# SocikPI.net
KiCad netlist of a schematic drawn in EAGLE
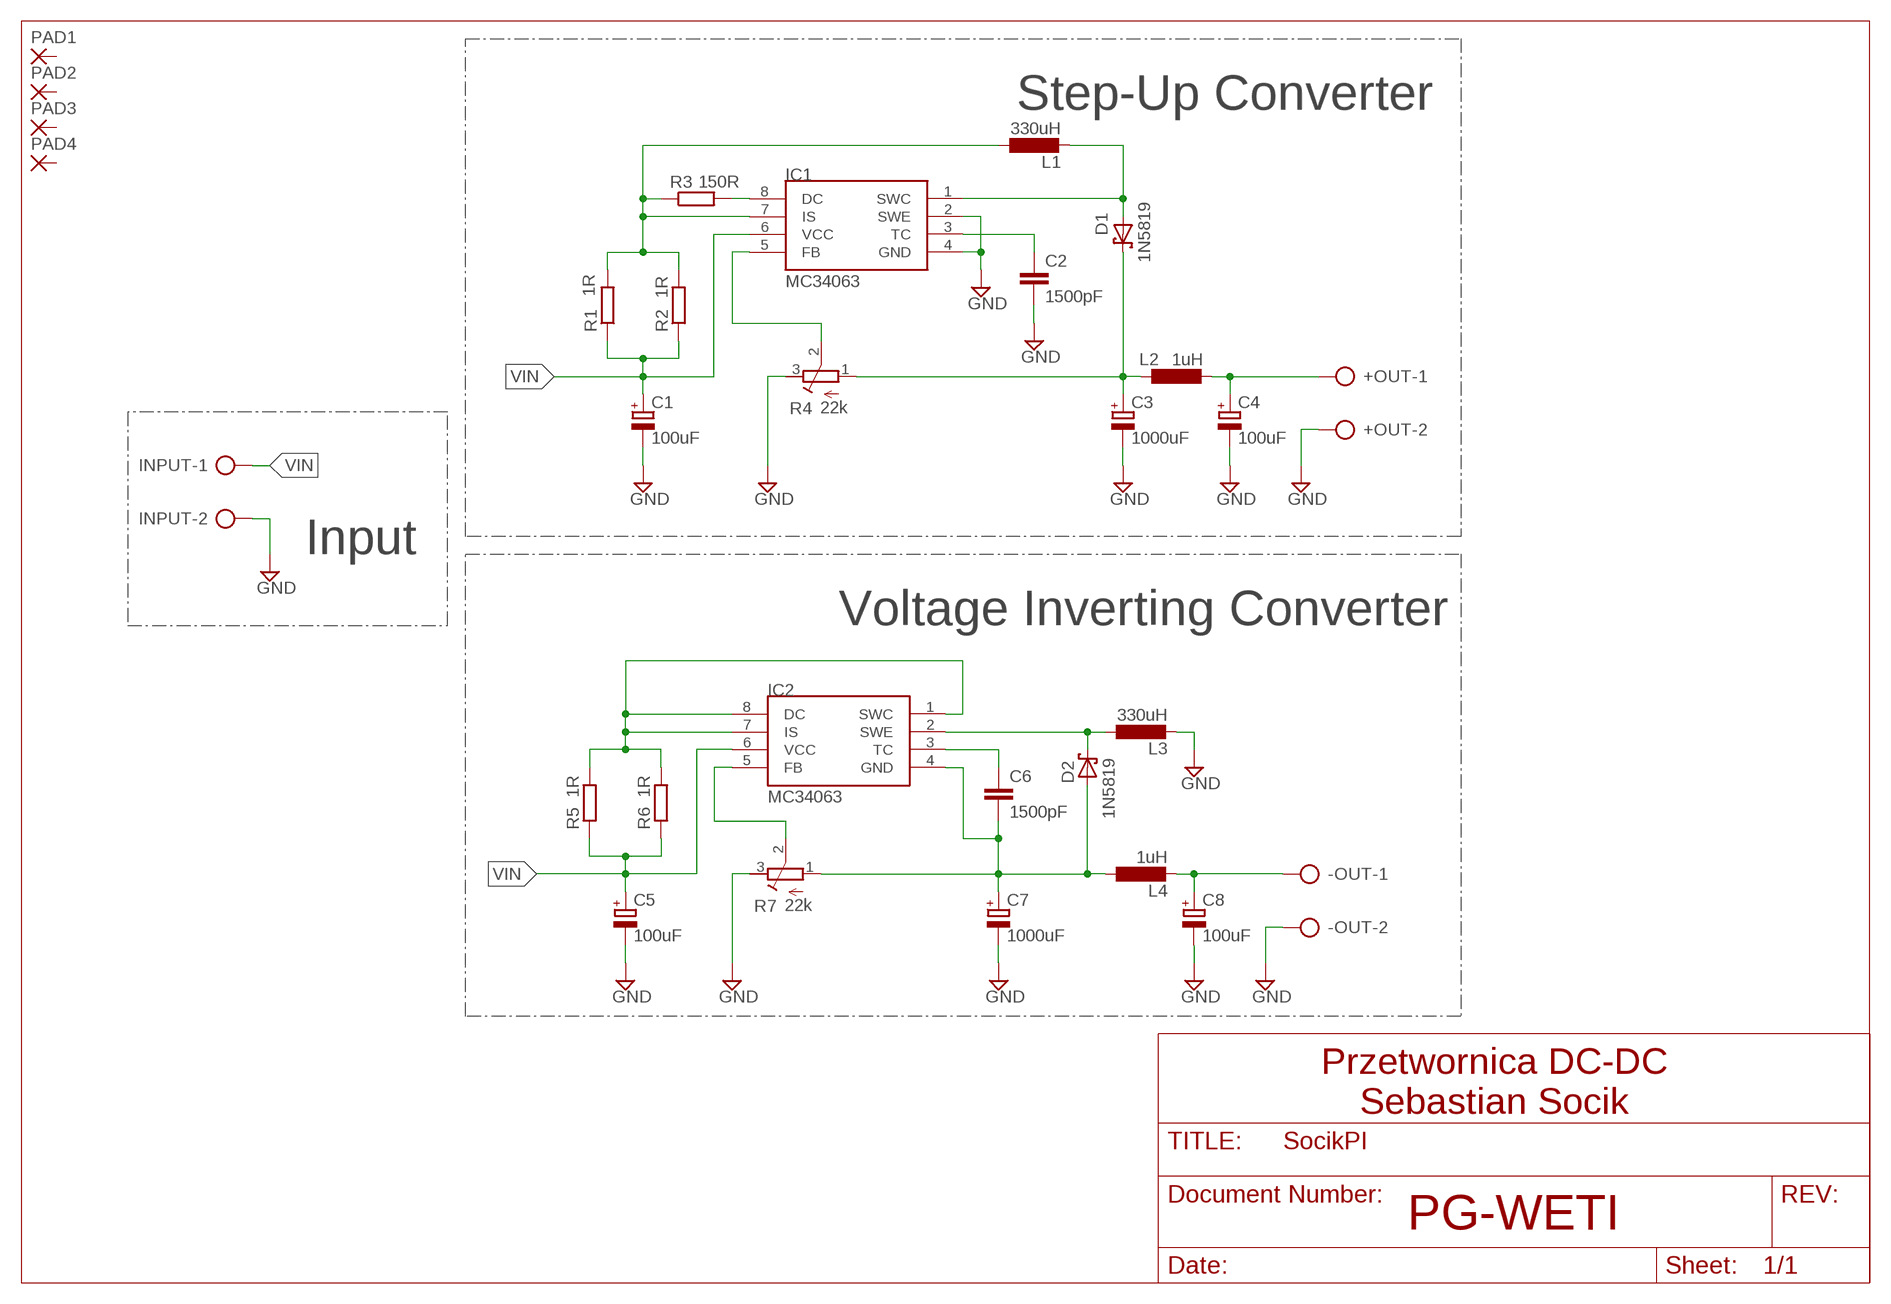
[diagram p0: schematic, sheet 1]

(export (version "E")
  (design (tool "Eeschema 10.0.6"))
  (components
    (comp (ref "+OUT")
      (value "CON-PTR500_AK500/2")
      (footprint "eagle-import:CON-PTR500_AK500_2")
      (libsource (lib "eagle-import") (part "CON-PTR500_AK500/2"))
    )
    (comp (ref "-OUT")
      (value "CON-PTR500_AK500/2")
      (footprint "eagle-import:CON-PTR500_AK500_2")
      (libsource (lib "eagle-import") (part "CON-PTR500_AK500/2"))
    )
    (comp (ref "C1")
      (value "100uF")
      (footprint "eagle-import:RCL_E2,5-7")
      (libsource (lib "eagle-import") (part "RCL_CPOL-EUE2.5-7"))
    )
    (comp (ref "C2")
      (value "1500pF")
      (footprint "eagle-import:C1206")
      (libsource (lib "eagle-import") (part "C-EUC1206"))
    )
    (comp (ref "C3")
      (value "1000uF")
      (footprint "eagle-import:RCL_E5-10,5")
      (libsource (lib "eagle-import") (part "RCL_CPOL-EUE5-10.5"))
    )
    (comp (ref "C4")
      (value "100uF")
      (footprint "eagle-import:RCL_E2,5-7")
      (libsource (lib "eagle-import") (part "RCL_CPOL-EUE2.5-7"))
    )
    (comp (ref "C5")
      (value "100uF")
      (footprint "eagle-import:RCL_E2,5-7")
      (libsource (lib "eagle-import") (part "RCL_CPOL-EUE2.5-7"))
    )
    (comp (ref "C6")
      (value "1500pF")
      (footprint "eagle-import:C1206")
      (libsource (lib "eagle-import") (part "C-EUC1206"))
    )
    (comp (ref "C7")
      (value "1000uF")
      (footprint "eagle-import:RCL_E5-10,5")
      (libsource (lib "eagle-import") (part "RCL_CPOL-EUE5-10.5"))
    )
    (comp (ref "C8")
      (value "100uF")
      (footprint "eagle-import:RCL_E2,5-7")
      (libsource (lib "eagle-import") (part "RCL_CPOL-EUE2.5-7"))
    )
    (comp (ref "D1")
      (value "1N5819")
      (footprint "eagle-import:DIODE_DO41-7.6")
      (libsource (lib "eagle-import") (part "DIODE_1N5819-B"))
    )
    (comp (ref "D2")
      (value "1N5819")
      (footprint "eagle-import:DIODE_DO41-7.6")
      (libsource (lib "eagle-import") (part "DIODE_1N5819-B"))
    )
    (comp (ref "IC1")
      (value "MC34063")
      (footprint "eagle-import:MC34063_DIL08")
      (libsource (lib "eagle-import") (part "MC34063_MC34063AP"))
    )
    (comp (ref "IC2")
      (value "MC34063")
      (footprint "eagle-import:MC34063_DIL08")
      (libsource (lib "eagle-import") (part "MC34063_MC34063AP"))
    )
    (comp (ref "INPUT")
      (value "CON-PTR500_AK500/2")
      (footprint "eagle-import:CON-PTR500_AK500_2")
      (libsource (lib "eagle-import") (part "CON-PTR500_AK500/2"))
    )
    (comp (ref "L1")
      (value "330uH")
      (footprint "eagle-import:RCL_0207_10")
      (libsource (lib "eagle-import") (part "RCL_L-EU0207/10"))
    )
    (comp (ref "L2")
      (value "1uH")
      (footprint "eagle-import:RCL_0207_10")
      (libsource (lib "eagle-import") (part "RCL_L-EU0207/10"))
    )
    (comp (ref "L3")
      (value "330uH")
      (footprint "eagle-import:RCL_0207_10")
      (libsource (lib "eagle-import") (part "RCL_L-EU0207/10"))
    )
    (comp (ref "L4")
      (value "1uH")
      (footprint "eagle-import:RCL_0207_10")
      (libsource (lib "eagle-import") (part "RCL_L-EU0207/10"))
    )
    (comp (ref "PAD1")
      (value "2,54/1,1")
      (footprint "eagle-import:2,54_1,1")
      (libsource (lib "eagle-import") (part "2,54/1,1"))
    )
    (comp (ref "PAD2")
      (value "2,54/1,1")
      (footprint "eagle-import:2,54_1,1")
      (libsource (lib "eagle-import") (part "2,54/1,1"))
    )
    (comp (ref "PAD3")
      (value "2,54/1,1")
      (footprint "eagle-import:2,54_1,1")
      (libsource (lib "eagle-import") (part "2,54/1,1"))
    )
    (comp (ref "PAD4")
      (value "2,54/1,1")
      (footprint "eagle-import:2,54_1,1")
      (libsource (lib "eagle-import") (part "2,54/1,1"))
    )
    (comp (ref "R1")
      (value "1R")
      (footprint "eagle-import:R1206")
      (libsource (lib "eagle-import") (part "R-EU_R1206"))
    )
    (comp (ref "R2")
      (value "1R")
      (footprint "eagle-import:R1206")
      (libsource (lib "eagle-import") (part "R-EU_R1206"))
    )
    (comp (ref "R3")
      (value "150R")
      (footprint "eagle-import:R1206")
      (libsource (lib "eagle-import") (part "R-EU_R1206"))
    )
    (comp (ref "R4")
      (value "22k")
      (footprint "eagle-import:PRZETWORNICAL_RTRIMCT32")
      (libsource (lib "eagle-import") (part "PRZETWORNICAL_RTRIMCT32"))
    )
    (comp (ref "R5")
      (value "1R")
      (footprint "eagle-import:R1206")
      (libsource (lib "eagle-import") (part "R-EU_R1206"))
    )
    (comp (ref "R6")
      (value "1R")
      (footprint "eagle-import:R1206")
      (libsource (lib "eagle-import") (part "R-EU_R1206"))
    )
    (comp (ref "R7")
      (value "22k")
      (footprint "eagle-import:PRZETWORNICAL_RTRIMCT32")
      (libsource (lib "eagle-import") (part "PRZETWORNICAL_RTRIMCT32"))
    )
  )
  (nets
    (net (code "1") (name "GND") (class "Default")
      (node (ref "+OUT") (pin "2") (pinfunction "KL_2") (pintype "passive"))
      (node (ref "-OUT") (pin "2") (pinfunction "KL_2") (pintype "passive"))
      (node (ref "C1") (pin "-") (pinfunction "-_-") (pintype "passive"))
      (node (ref "C2") (pin "2") (pinfunction "2_2") (pintype "passive"))
      (node (ref "C3") (pin "-") (pinfunction "-_-") (pintype "passive"))
      (node (ref "C4") (pin "-") (pinfunction "-_-") (pintype "passive"))
      (node (ref "C5") (pin "-") (pinfunction "-_-") (pintype "passive"))
      (node (ref "C7") (pin "-") (pinfunction "-_-") (pintype "passive"))
      (node (ref "C8") (pin "-") (pinfunction "-_-") (pintype "passive"))
      (node (ref "IC1") (pin "2") (pinfunction "SWE_2") (pintype "passive"))
      (node (ref "IC1") (pin "4") (pinfunction "GND_4") (pintype "passive"))
      (node (ref "INPUT") (pin "2") (pinfunction "KL_2") (pintype "passive"))
      (node (ref "L3") (pin "2") (pinfunction "2_2") (pintype "passive"))
      (node (ref "R4") (pin "3") (pinfunction "E_3") (pintype "passive"))
      (node (ref "R7") (pin "3") (pinfunction "E_3") (pintype "passive"))
    )
    (net (code "2") (name "Net-(+OUTA-KL)") (class "Default")
      (node (ref "+OUT") (pin "1") (pinfunction "KL_1") (pintype "passive"))
      (node (ref "C4") (pin "+") (pinfunction "+_+") (pintype "passive"))
      (node (ref "L2") (pin "2") (pinfunction "2_2") (pintype "passive"))
    )
    (net (code "3") (name "Net-(-OUTA-KL)") (class "Default")
      (node (ref "-OUT") (pin "1") (pinfunction "KL_1") (pintype "passive"))
      (node (ref "C8") (pin "+") (pinfunction "+_+") (pintype "passive"))
      (node (ref "L4") (pin "2") (pinfunction "2_2") (pintype "passive"))
    )
    (net (code "4") (name "Net-(IC1-DC)") (class "Default")
      (node (ref "IC1") (pin "8") (pinfunction "DC_8") (pintype "passive"))
      (node (ref "R3") (pin "2") (pinfunction "2_2") (pintype "passive"))
    )
    (net (code "5") (name "Net-(IC1-FB)") (class "Default")
      (node (ref "IC1") (pin "5") (pinfunction "FB_5") (pintype "passive"))
      (node (ref "R4") (pin "2") (pinfunction "S_2") (pintype "passive"))
    )
    (net (code "6") (name "Net-(IC1-IS)") (class "Default")
      (node (ref "IC1") (pin "7") (pinfunction "IS_7") (pintype "passive"))
      (node (ref "L1") (pin "1") (pinfunction "1_1") (pintype "passive"))
      (node (ref "R1") (pin "2") (pinfunction "2_2") (pintype "passive"))
      (node (ref "R2") (pin "2") (pinfunction "2_2") (pintype "passive"))
      (node (ref "R3") (pin "1") (pinfunction "1_1") (pintype "passive"))
    )
    (net (code "7") (name "Net-(IC1-SWC)") (class "Default")
      (node (ref "D1") (pin "A") (pinfunction "A_A") (pintype "passive"))
      (node (ref "IC1") (pin "1") (pinfunction "SWC_1") (pintype "passive"))
      (node (ref "L1") (pin "2") (pinfunction "2_2") (pintype "passive"))
    )
    (net (code "8") (name "Net-(IC1-TC)") (class "Default")
      (node (ref "C2") (pin "1") (pinfunction "1_1") (pintype "passive"))
      (node (ref "IC1") (pin "3") (pinfunction "TC_3") (pintype "passive"))
    )
    (net (code "9") (name "Net-(IC2-DC)") (class "Default")
      (node (ref "IC2") (pin "1") (pinfunction "SWC_1") (pintype "passive"))
      (node (ref "IC2") (pin "7") (pinfunction "IS_7") (pintype "passive"))
      (node (ref "IC2") (pin "8") (pinfunction "DC_8") (pintype "passive"))
      (node (ref "R5") (pin "2") (pinfunction "2_2") (pintype "passive"))
      (node (ref "R6") (pin "2") (pinfunction "2_2") (pintype "passive"))
    )
    (net (code "10") (name "Net-(IC2-FB)") (class "Default")
      (node (ref "IC2") (pin "5") (pinfunction "FB_5") (pintype "passive"))
      (node (ref "R7") (pin "2") (pinfunction "S_2") (pintype "passive"))
    )
    (net (code "11") (name "Net-(IC2-GND)") (class "Default")
      (node (ref "C6") (pin "2") (pinfunction "2_2") (pintype "passive"))
      (node (ref "C7") (pin "+") (pinfunction "+_+") (pintype "passive"))
      (node (ref "D2") (pin "A") (pinfunction "A_A") (pintype "passive"))
      (node (ref "IC2") (pin "4") (pinfunction "GND_4") (pintype "passive"))
      (node (ref "L4") (pin "1") (pinfunction "1_1") (pintype "passive"))
      (node (ref "R7") (pin "1") (pinfunction "A_1") (pintype "passive"))
    )
    (net (code "12") (name "Net-(IC2-SWE)") (class "Default")
      (node (ref "D2") (pin "C") (pinfunction "C_C") (pintype "passive"))
      (node (ref "IC2") (pin "2") (pinfunction "SWE_2") (pintype "passive"))
      (node (ref "L3") (pin "1") (pinfunction "1_1") (pintype "passive"))
    )
    (net (code "13") (name "Net-(IC2-TC)") (class "Default")
      (node (ref "C6") (pin "1") (pinfunction "1_1") (pintype "passive"))
      (node (ref "IC2") (pin "3") (pinfunction "TC_3") (pintype "passive"))
    )
    (net (code "14") (name "Net-(R4-A)") (class "Default")
      (node (ref "C3") (pin "+") (pinfunction "+_+") (pintype "passive"))
      (node (ref "D1") (pin "C") (pinfunction "C_C") (pintype "passive"))
      (node (ref "L2") (pin "1") (pinfunction "1_1") (pintype "passive"))
      (node (ref "R4") (pin "1") (pinfunction "A_1") (pintype "passive"))
    )
    (net (code "15") (name "VIN") (class "Default")
      (node (ref "C1") (pin "+") (pinfunction "+_+") (pintype "passive"))
      (node (ref "C5") (pin "+") (pinfunction "+_+") (pintype "passive"))
      (node (ref "IC1") (pin "6") (pinfunction "VCC_6") (pintype "passive"))
      (node (ref "IC2") (pin "6") (pinfunction "VCC_6") (pintype "passive"))
      (node (ref "INPUT") (pin "1") (pinfunction "KL_1") (pintype "passive"))
      (node (ref "R1") (pin "1") (pinfunction "1_1") (pintype "passive"))
      (node (ref "R2") (pin "1") (pinfunction "1_1") (pintype "passive"))
      (node (ref "R5") (pin "1") (pinfunction "1_1") (pintype "passive"))
      (node (ref "R6") (pin "1") (pinfunction "1_1") (pintype "passive"))
    )
    (net (code "16") (name "unconnected-(PAD1-P-Pad1)") (class "Default")
      (node (ref "PAD1") (pin "1") (pinfunction "P_1") (pintype "passive"))
    )
    (net (code "17") (name "unconnected-(PAD2-P-Pad1)") (class "Default")
      (node (ref "PAD2") (pin "1") (pinfunction "P_1") (pintype "passive"))
    )
    (net (code "18") (name "unconnected-(PAD3-P-Pad1)") (class "Default")
      (node (ref "PAD3") (pin "1") (pinfunction "P_1") (pintype "passive"))
    )
    (net (code "19") (name "unconnected-(PAD4-P-Pad1)") (class "Default")
      (node (ref "PAD4") (pin "1") (pinfunction "P_1") (pintype "passive"))
    )
  )
)
